# sch.net
KiCad netlist of a schematic drawn in EasyEDA
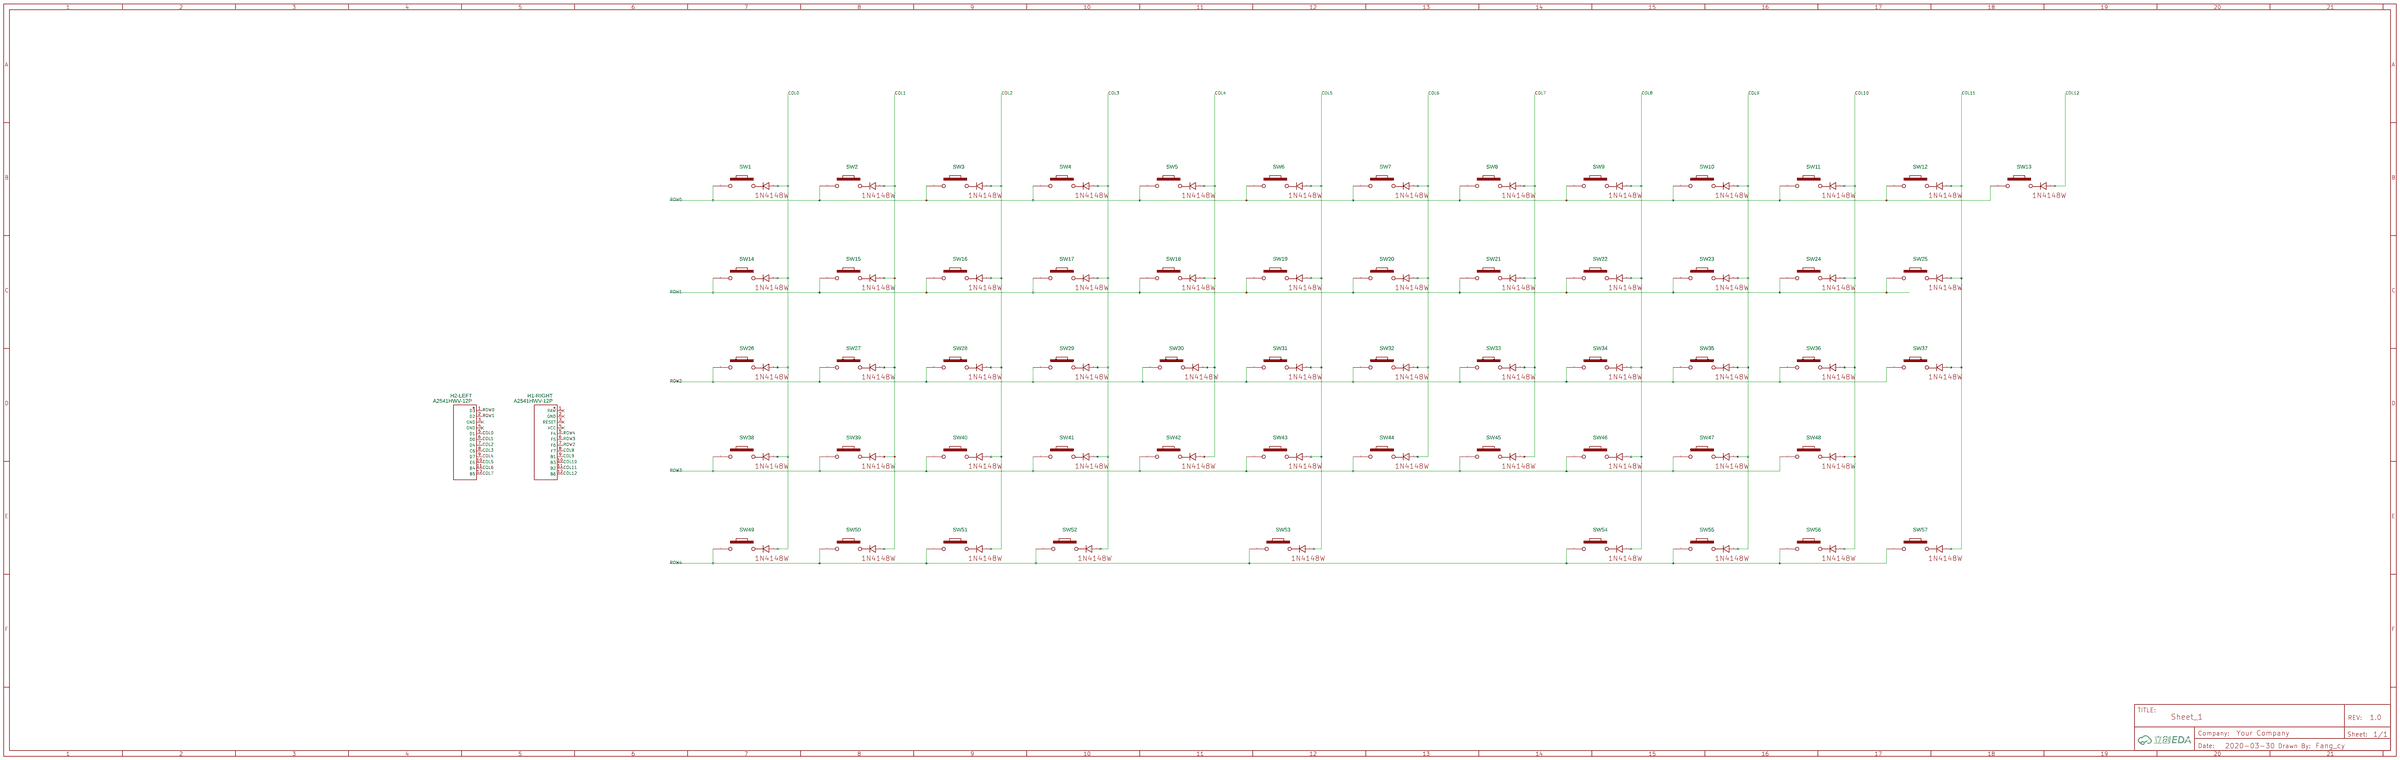
[diagram p0: schematic sheet]

(export (version "E")
  (design (tool "Eeschema 10.0.6"))
  (components
    (comp (ref "H1-RIGHT")
      (value "A2541HWV-12P")
      (fields (field (name "BOM_Supplier Part") "C225509"))
      (libsource (lib "") (part "A2541HWV-12P"))
    )
    (comp (ref "H2-LEFT")
      (value "A2541HWV-12P")
      (fields (field (name "BOM_Supplier Part") "C225509"))
      (libsource (lib "") (part "A2541HWV-12P_1"))
    )
    (comp (ref "SW1")
      (value "CHERRY-Kaih+diode")
      (fields (field (name "BOM_Manufacturer Part") "00"))
      (libsource (lib "") (part "CHERRY-Kaih+diode"))
    )
    (comp (ref "SW2")
      (value "CHERRY-Kaih+diode")
      (fields (field (name "BOM_Manufacturer Part") "00"))
      (libsource (lib "") (part "CHERRY-Kaih+diode"))
    )
    (comp (ref "SW3")
      (value "CHERRY-Kaih+diode")
      (fields (field (name "BOM_Manufacturer Part") "00"))
      (libsource (lib "") (part "CHERRY-Kaih+diode"))
    )
    (comp (ref "SW4")
      (value "CHERRY-Kaih+diode")
      (fields (field (name "BOM_Manufacturer Part") "00"))
      (libsource (lib "") (part "CHERRY-Kaih+diode"))
    )
    (comp (ref "SW5")
      (value "CHERRY-Kaih+diode")
      (fields (field (name "BOM_Manufacturer Part") "00"))
      (libsource (lib "") (part "CHERRY-Kaih+diode"))
    )
    (comp (ref "SW6")
      (value "CHERRY-Kaih+diode")
      (fields (field (name "BOM_Manufacturer Part") "00"))
      (libsource (lib "") (part "CHERRY-Kaih+diode"))
    )
    (comp (ref "SW7")
      (value "CHERRY-Kaih+diode")
      (fields (field (name "BOM_Manufacturer Part") "00"))
      (libsource (lib "") (part "CHERRY-Kaih+diode"))
    )
    (comp (ref "SW8")
      (value "CHERRY-Kaih+diode")
      (fields (field (name "BOM_Manufacturer Part") "00"))
      (libsource (lib "") (part "CHERRY-Kaih+diode"))
    )
    (comp (ref "SW9")
      (value "CHERRY-Kaih+diode")
      (fields (field (name "BOM_Manufacturer Part") "00"))
      (libsource (lib "") (part "CHERRY-Kaih+diode"))
    )
    (comp (ref "SW10")
      (value "CHERRY-Kaih+diode")
      (fields (field (name "BOM_Manufacturer Part") "00"))
      (libsource (lib "") (part "CHERRY-Kaih+diode"))
    )
    (comp (ref "SW11")
      (value "CHERRY-Kaih+diode")
      (fields (field (name "BOM_Manufacturer Part") "00"))
      (libsource (lib "") (part "CHERRY-Kaih+diode"))
    )
    (comp (ref "SW12")
      (value "CHERRY-Kaih+diode")
      (fields (field (name "BOM_Manufacturer Part") "00"))
      (libsource (lib "") (part "CHERRY-Kaih+diode"))
    )
    (comp (ref "SW13")
      (value "CHERRY-Kaih+diode")
      (fields (field (name "BOM_Manufacturer Part") "00"))
      (libsource (lib "") (part "CHERRY-Kaih+diode"))
    )
    (comp (ref "SW14")
      (value "CHERRY-Kaih+diode")
      (fields (field (name "BOM_Manufacturer Part") "00"))
      (libsource (lib "") (part "CHERRY-Kaih+diode"))
    )
    (comp (ref "SW15")
      (value "CHERRY-Kaih+diode")
      (fields (field (name "BOM_Manufacturer Part") "00"))
      (libsource (lib "") (part "CHERRY-Kaih+diode"))
    )
    (comp (ref "SW16")
      (value "CHERRY-Kaih+diode")
      (fields (field (name "BOM_Manufacturer Part") "00"))
      (libsource (lib "") (part "CHERRY-Kaih+diode"))
    )
    (comp (ref "SW17")
      (value "CHERRY-Kaih+diode")
      (fields (field (name "BOM_Manufacturer Part") "00"))
      (libsource (lib "") (part "CHERRY-Kaih+diode"))
    )
    (comp (ref "SW18")
      (value "CHERRY-Kaih+diode")
      (fields (field (name "BOM_Manufacturer Part") "00"))
      (libsource (lib "") (part "CHERRY-Kaih+diode"))
    )
    (comp (ref "SW19")
      (value "CHERRY-Kaih+diode")
      (fields (field (name "BOM_Manufacturer Part") "00"))
      (libsource (lib "") (part "CHERRY-Kaih+diode"))
    )
    (comp (ref "SW20")
      (value "CHERRY-Kaih+diode")
      (fields (field (name "BOM_Manufacturer Part") "00"))
      (libsource (lib "") (part "CHERRY-Kaih+diode"))
    )
    (comp (ref "SW21")
      (value "CHERRY-Kaih+diode")
      (fields (field (name "BOM_Manufacturer Part") "00"))
      (libsource (lib "") (part "CHERRY-Kaih+diode"))
    )
    (comp (ref "SW22")
      (value "CHERRY-Kaih+diode")
      (fields (field (name "BOM_Manufacturer Part") "00"))
      (libsource (lib "") (part "CHERRY-Kaih+diode"))
    )
    (comp (ref "SW23")
      (value "CHERRY-Kaih+diode")
      (fields (field (name "BOM_Manufacturer Part") "00"))
      (libsource (lib "") (part "CHERRY-Kaih+diode"))
    )
    (comp (ref "SW24")
      (value "CHERRY-Kaih+diode")
      (fields (field (name "BOM_Manufacturer Part") "00"))
      (libsource (lib "") (part "CHERRY-Kaih+diode"))
    )
    (comp (ref "SW25")
      (value "CHERRY-Kaih+diode")
      (fields (field (name "BOM_Manufacturer Part") "00"))
      (libsource (lib "") (part "CHERRY-Kaih+diode"))
    )
    (comp (ref "SW26")
      (value "CHERRY-Kaih+diode")
      (fields (field (name "BOM_Manufacturer Part") "00"))
      (libsource (lib "") (part "CHERRY-Kaih+diode_2"))
    )
    (comp (ref "SW27")
      (value "CHERRY-Kaih+diode")
      (fields (field (name "BOM_Manufacturer Part") "00"))
      (libsource (lib "") (part "CHERRY-Kaih+diode_2"))
    )
    (comp (ref "SW28")
      (value "CHERRY-Kaih+diode")
      (fields (field (name "BOM_Manufacturer Part") "00"))
      (libsource (lib "") (part "CHERRY-Kaih+diode_2"))
    )
    (comp (ref "SW29")
      (value "CHERRY-Kaih+diode")
      (fields (field (name "BOM_Manufacturer Part") "00"))
      (libsource (lib "") (part "CHERRY-Kaih+diode_2"))
    )
    (comp (ref "SW30")
      (value "CHERRY-Kaih+diode")
      (fields (field (name "BOM_Manufacturer Part") "00"))
      (libsource (lib "") (part "CHERRY-Kaih+diode_2"))
    )
    (comp (ref "SW31")
      (value "CHERRY-Kaih+diode")
      (fields (field (name "BOM_Manufacturer Part") "00"))
      (libsource (lib "") (part "CHERRY-Kaih+diode_2"))
    )
    (comp (ref "SW32")
      (value "CHERRY-Kaih+diode")
      (fields (field (name "BOM_Manufacturer Part") "00"))
      (libsource (lib "") (part "CHERRY-Kaih+diode_2"))
    )
    (comp (ref "SW33")
      (value "CHERRY-Kaih+diode")
      (fields (field (name "BOM_Manufacturer Part") "00"))
      (libsource (lib "") (part "CHERRY-Kaih+diode_2"))
    )
    (comp (ref "SW34")
      (value "CHERRY-Kaih+diode")
      (fields (field (name "BOM_Manufacturer Part") "00"))
      (libsource (lib "") (part "CHERRY-Kaih+diode_2"))
    )
    (comp (ref "SW35")
      (value "CHERRY-Kaih+diode")
      (fields (field (name "BOM_Manufacturer Part") "00"))
      (libsource (lib "") (part "CHERRY-Kaih+diode_2"))
    )
    (comp (ref "SW36")
      (value "CHERRY-Kaih+diode")
      (fields (field (name "BOM_Manufacturer Part") "00"))
      (libsource (lib "") (part "CHERRY-Kaih+diode_2"))
    )
    (comp (ref "SW37")
      (value "CHERRY-Kaih+diode")
      (fields (field (name "BOM_Manufacturer Part") "00"))
      (libsource (lib "") (part "CHERRY-Kaih+diode_2"))
    )
    (comp (ref "SW38")
      (value "CHERRY-Kaih+diode")
      (fields (field (name "BOM_Manufacturer Part") "00"))
      (libsource (lib "") (part "CHERRY-Kaih+diode"))
    )
    (comp (ref "SW39")
      (value "CHERRY-Kaih+diode")
      (fields (field (name "BOM_Manufacturer Part") "00"))
      (libsource (lib "") (part "CHERRY-Kaih+diode"))
    )
    (comp (ref "SW40")
      (value "CHERRY-Kaih+diode")
      (fields (field (name "BOM_Manufacturer Part") "00"))
      (libsource (lib "") (part "CHERRY-Kaih+diode"))
    )
    (comp (ref "SW41")
      (value "CHERRY-Kaih+diode")
      (fields (field (name "BOM_Manufacturer Part") "00"))
      (libsource (lib "") (part "CHERRY-Kaih+diode"))
    )
    (comp (ref "SW42")
      (value "CHERRY-Kaih+diode")
      (fields (field (name "BOM_Manufacturer Part") "00"))
      (libsource (lib "") (part "CHERRY-Kaih+diode"))
    )
    (comp (ref "SW43")
      (value "CHERRY-Kaih+diode")
      (fields (field (name "BOM_Manufacturer Part") "00"))
      (libsource (lib "") (part "CHERRY-Kaih+diode"))
    )
    (comp (ref "SW44")
      (value "CHERRY-Kaih+diode")
      (fields (field (name "BOM_Manufacturer Part") "00"))
      (libsource (lib "") (part "CHERRY-Kaih+diode"))
    )
    (comp (ref "SW45")
      (value "CHERRY-Kaih+diode")
      (fields (field (name "BOM_Manufacturer Part") "00"))
      (libsource (lib "") (part "CHERRY-Kaih+diode"))
    )
    (comp (ref "SW46")
      (value "CHERRY-Kaih+diode")
      (fields (field (name "BOM_Manufacturer Part") "00"))
      (libsource (lib "") (part "CHERRY-Kaih+diode"))
    )
    (comp (ref "SW47")
      (value "CHERRY-Kaih+diode")
      (fields (field (name "BOM_Manufacturer Part") "00"))
      (libsource (lib "") (part "CHERRY-Kaih+diode"))
    )
    (comp (ref "SW48")
      (value "CHERRY-Kaih+diode")
      (fields (field (name "BOM_Manufacturer Part") "00"))
      (libsource (lib "") (part "CHERRY-Kaih+diode"))
    )
    (comp (ref "SW49")
      (value "CHERRY-Kaih+diode")
      (fields (field (name "BOM_Manufacturer Part") "00"))
      (libsource (lib "") (part "CHERRY-Kaih+diode_1"))
    )
    (comp (ref "SW50")
      (value "CHERRY-Kaih+diode")
      (fields (field (name "BOM_Manufacturer Part") "00"))
      (libsource (lib "") (part "CHERRY-Kaih+diode_1"))
    )
    (comp (ref "SW51")
      (value "CHERRY-Kaih+diode")
      (fields (field (name "BOM_Manufacturer Part") "00"))
      (libsource (lib "") (part "CHERRY-Kaih+diode_1"))
    )
    (comp (ref "SW52")
      (value "CHERRY-Kaih+diode")
      (fields (field (name "BOM_Manufacturer Part") "00"))
      (libsource (lib "") (part "CHERRY-Kaih+diode_1"))
    )
    (comp (ref "SW53")
      (value "CHERRY-Kaih+diode")
      (fields (field (name "BOM_Manufacturer Part") "00"))
      (libsource (lib "") (part "CHERRY-Kaih+diode_1"))
    )
    (comp (ref "SW54")
      (value "CHERRY-Kaih+diode")
      (fields (field (name "BOM_Manufacturer Part") "00"))
      (libsource (lib "") (part "CHERRY-Kaih+diode_1"))
    )
    (comp (ref "SW55")
      (value "CHERRY-Kaih+diode")
      (fields (field (name "BOM_Manufacturer Part") "00"))
      (libsource (lib "") (part "CHERRY-Kaih+diode_1"))
    )
    (comp (ref "SW56")
      (value "CHERRY-Kaih+diode")
      (fields (field (name "BOM_Manufacturer Part") "00"))
      (libsource (lib "") (part "CHERRY-Kaih+diode_1"))
    )
    (comp (ref "SW57")
      (value "CHERRY-Kaih+diode")
      (fields (field (name "BOM_Manufacturer Part") "00"))
      (libsource (lib "") (part "CHERRY-Kaih+diode_1"))
    )
  )
  (nets
    (net (code "1") (name "/COL0") (class "Default")
      (node (ref "H2-LEFT") (pin "5") (pinfunction "D1_5") (pintype "unspecified"))
      (node (ref "SW1") (pin "col") (pinfunction "col_col") (pintype "unspecified"))
      (node (ref "SW14") (pin "col") (pinfunction "col_col") (pintype "unspecified"))
      (node (ref "SW26") (pin "col") (pinfunction "col_col") (pintype "unspecified"))
      (node (ref "SW38") (pin "col") (pinfunction "col_col") (pintype "unspecified"))
      (node (ref "SW49") (pin "col") (pinfunction "col_col") (pintype "unspecified"))
    )
    (net (code "2") (name "/COL1") (class "Default")
      (node (ref "H2-LEFT") (pin "6") (pinfunction "D0_6") (pintype "unspecified"))
      (node (ref "SW15") (pin "col") (pinfunction "col_col") (pintype "unspecified"))
      (node (ref "SW2") (pin "col") (pinfunction "col_col") (pintype "unspecified"))
      (node (ref "SW27") (pin "col") (pinfunction "col_col") (pintype "unspecified"))
      (node (ref "SW39") (pin "col") (pinfunction "col_col") (pintype "unspecified"))
      (node (ref "SW50") (pin "col") (pinfunction "col_col") (pintype "unspecified"))
    )
    (net (code "3") (name "/COL2") (class "Default")
      (node (ref "H2-LEFT") (pin "7") (pinfunction "D4_7") (pintype "unspecified"))
      (node (ref "SW16") (pin "col") (pinfunction "col_col") (pintype "unspecified"))
      (node (ref "SW28") (pin "col") (pinfunction "col_col") (pintype "unspecified"))
      (node (ref "SW3") (pin "col") (pinfunction "col_col") (pintype "unspecified"))
      (node (ref "SW40") (pin "col") (pinfunction "col_col") (pintype "unspecified"))
      (node (ref "SW51") (pin "col") (pinfunction "col_col") (pintype "unspecified"))
    )
    (net (code "4") (name "/COL3") (class "Default")
      (node (ref "H2-LEFT") (pin "8") (pinfunction "C6_8") (pintype "unspecified"))
      (node (ref "SW17") (pin "col") (pinfunction "col_col") (pintype "unspecified"))
      (node (ref "SW29") (pin "col") (pinfunction "col_col") (pintype "unspecified"))
      (node (ref "SW4") (pin "col") (pinfunction "col_col") (pintype "unspecified"))
      (node (ref "SW41") (pin "col") (pinfunction "col_col") (pintype "unspecified"))
      (node (ref "SW52") (pin "col") (pinfunction "col_col") (pintype "unspecified"))
    )
    (net (code "5") (name "/COL4") (class "Default")
      (node (ref "H2-LEFT") (pin "9") (pinfunction "D7_9") (pintype "unspecified"))
      (node (ref "SW18") (pin "col") (pinfunction "col_col") (pintype "unspecified"))
      (node (ref "SW30") (pin "col") (pinfunction "col_col") (pintype "unspecified"))
      (node (ref "SW42") (pin "col") (pinfunction "col_col") (pintype "unspecified"))
      (node (ref "SW5") (pin "col") (pinfunction "col_col") (pintype "unspecified"))
    )
    (net (code "6") (name "/COL5") (class "Default")
      (node (ref "H2-LEFT") (pin "10") (pinfunction "E6_10") (pintype "unspecified"))
      (node (ref "SW19") (pin "col") (pinfunction "col_col") (pintype "unspecified"))
      (node (ref "SW31") (pin "col") (pinfunction "col_col") (pintype "unspecified"))
      (node (ref "SW43") (pin "col") (pinfunction "col_col") (pintype "unspecified"))
      (node (ref "SW53") (pin "col") (pinfunction "col_col") (pintype "unspecified"))
      (node (ref "SW6") (pin "col") (pinfunction "col_col") (pintype "unspecified"))
    )
    (net (code "7") (name "/COL6") (class "Default")
      (node (ref "H2-LEFT") (pin "11") (pinfunction "B4_11") (pintype "unspecified"))
      (node (ref "SW20") (pin "col") (pinfunction "col_col") (pintype "unspecified"))
      (node (ref "SW32") (pin "col") (pinfunction "col_col") (pintype "unspecified"))
      (node (ref "SW44") (pin "col") (pinfunction "col_col") (pintype "unspecified"))
      (node (ref "SW7") (pin "col") (pinfunction "col_col") (pintype "unspecified"))
    )
    (net (code "8") (name "/COL7") (class "Default")
      (node (ref "H2-LEFT") (pin "12") (pinfunction "B5_12") (pintype "unspecified"))
      (node (ref "SW21") (pin "col") (pinfunction "col_col") (pintype "unspecified"))
      (node (ref "SW33") (pin "col") (pinfunction "col_col") (pintype "unspecified"))
      (node (ref "SW45") (pin "col") (pinfunction "col_col") (pintype "unspecified"))
      (node (ref "SW8") (pin "col") (pinfunction "col_col") (pintype "unspecified"))
    )
    (net (code "9") (name "/COL8") (class "Default")
      (node (ref "H1-RIGHT") (pin "8") (pinfunction "F7_8") (pintype "unspecified"))
      (node (ref "SW22") (pin "col") (pinfunction "col_col") (pintype "unspecified"))
      (node (ref "SW34") (pin "col") (pinfunction "col_col") (pintype "unspecified"))
      (node (ref "SW46") (pin "col") (pinfunction "col_col") (pintype "unspecified"))
      (node (ref "SW54") (pin "col") (pinfunction "col_col") (pintype "unspecified"))
      (node (ref "SW9") (pin "col") (pinfunction "col_col") (pintype "unspecified"))
    )
    (net (code "10") (name "/COL9") (class "Default")
      (node (ref "H1-RIGHT") (pin "9") (pinfunction "B1_9") (pintype "unspecified"))
      (node (ref "SW10") (pin "col") (pinfunction "col_col") (pintype "unspecified"))
      (node (ref "SW23") (pin "col") (pinfunction "col_col") (pintype "unspecified"))
      (node (ref "SW35") (pin "col") (pinfunction "col_col") (pintype "unspecified"))
      (node (ref "SW47") (pin "col") (pinfunction "col_col") (pintype "unspecified"))
      (node (ref "SW55") (pin "col") (pinfunction "col_col") (pintype "unspecified"))
    )
    (net (code "11") (name "/COL10") (class "Default")
      (node (ref "H1-RIGHT") (pin "10") (pinfunction "B3_10") (pintype "unspecified"))
      (node (ref "SW11") (pin "col") (pinfunction "col_col") (pintype "unspecified"))
      (node (ref "SW24") (pin "col") (pinfunction "col_col") (pintype "unspecified"))
      (node (ref "SW36") (pin "col") (pinfunction "col_col") (pintype "unspecified"))
      (node (ref "SW48") (pin "col") (pinfunction "col_col") (pintype "unspecified"))
      (node (ref "SW56") (pin "col") (pinfunction "col_col") (pintype "unspecified"))
    )
    (net (code "12") (name "/COL11") (class "Default")
      (node (ref "H1-RIGHT") (pin "11") (pinfunction "B2_11") (pintype "unspecified"))
      (node (ref "SW12") (pin "col") (pinfunction "col_col") (pintype "unspecified"))
      (node (ref "SW25") (pin "col") (pinfunction "col_col") (pintype "unspecified"))
      (node (ref "SW37") (pin "col") (pinfunction "col_col") (pintype "unspecified"))
      (node (ref "SW57") (pin "col") (pinfunction "col_col") (pintype "unspecified"))
    )
    (net (code "13") (name "/COL12") (class "Default")
      (node (ref "H1-RIGHT") (pin "12") (pinfunction "B6_12") (pintype "unspecified"))
      (node (ref "SW13") (pin "col") (pinfunction "col_col") (pintype "unspecified"))
    )
    (net (code "14") (name "/ROW0") (class "Default")
      (node (ref "H2-LEFT") (pin "1") (pinfunction "D3_1") (pintype "unspecified"))
      (node (ref "SW1") (pin "row") (pinfunction "row_row") (pintype "unspecified"))
      (node (ref "SW10") (pin "row") (pinfunction "row_row") (pintype "unspecified"))
      (node (ref "SW11") (pin "row") (pinfunction "row_row") (pintype "unspecified"))
      (node (ref "SW12") (pin "row") (pinfunction "row_row") (pintype "unspecified"))
      (node (ref "SW13") (pin "row") (pinfunction "row_row") (pintype "unspecified"))
      (node (ref "SW2") (pin "row") (pinfunction "row_row") (pintype "unspecified"))
      (node (ref "SW3") (pin "row") (pinfunction "row_row") (pintype "unspecified"))
      (node (ref "SW4") (pin "row") (pinfunction "row_row") (pintype "unspecified"))
      (node (ref "SW5") (pin "row") (pinfunction "row_row") (pintype "unspecified"))
      (node (ref "SW6") (pin "row") (pinfunction "row_row") (pintype "unspecified"))
      (node (ref "SW7") (pin "row") (pinfunction "row_row") (pintype "unspecified"))
      (node (ref "SW8") (pin "row") (pinfunction "row_row") (pintype "unspecified"))
      (node (ref "SW9") (pin "row") (pinfunction "row_row") (pintype "unspecified"))
    )
    (net (code "15") (name "/ROW1") (class "Default")
      (node (ref "H2-LEFT") (pin "2") (pinfunction "D2_2") (pintype "unspecified"))
      (node (ref "SW14") (pin "row") (pinfunction "row_row") (pintype "unspecified"))
      (node (ref "SW15") (pin "row") (pinfunction "row_row") (pintype "unspecified"))
      (node (ref "SW16") (pin "row") (pinfunction "row_row") (pintype "unspecified"))
      (node (ref "SW17") (pin "row") (pinfunction "row_row") (pintype "unspecified"))
      (node (ref "SW18") (pin "row") (pinfunction "row_row") (pintype "unspecified"))
      (node (ref "SW19") (pin "row") (pinfunction "row_row") (pintype "unspecified"))
      (node (ref "SW20") (pin "row") (pinfunction "row_row") (pintype "unspecified"))
      (node (ref "SW21") (pin "row") (pinfunction "row_row") (pintype "unspecified"))
      (node (ref "SW22") (pin "row") (pinfunction "row_row") (pintype "unspecified"))
      (node (ref "SW23") (pin "row") (pinfunction "row_row") (pintype "unspecified"))
      (node (ref "SW24") (pin "row") (pinfunction "row_row") (pintype "unspecified"))
      (node (ref "SW25") (pin "row") (pinfunction "row_row") (pintype "unspecified"))
    )
    (net (code "16") (name "/ROW2") (class "Default")
      (node (ref "H1-RIGHT") (pin "7") (pinfunction "F6_7") (pintype "unspecified"))
      (node (ref "SW26") (pin "row") (pinfunction "row_row") (pintype "unspecified"))
      (node (ref "SW27") (pin "row") (pinfunction "row_row") (pintype "unspecified"))
      (node (ref "SW28") (pin "row") (pinfunction "row_row") (pintype "unspecified"))
      (node (ref "SW29") (pin "row") (pinfunction "row_row") (pintype "unspecified"))
      (node (ref "SW30") (pin "row") (pinfunction "row_row") (pintype "unspecified"))
      (node (ref "SW31") (pin "row") (pinfunction "row_row") (pintype "unspecified"))
      (node (ref "SW32") (pin "row") (pinfunction "row_row") (pintype "unspecified"))
      (node (ref "SW33") (pin "row") (pinfunction "row_row") (pintype "unspecified"))
      (node (ref "SW34") (pin "row") (pinfunction "row_row") (pintype "unspecified"))
      (node (ref "SW35") (pin "row") (pinfunction "row_row") (pintype "unspecified"))
      (node (ref "SW36") (pin "row") (pinfunction "row_row") (pintype "unspecified"))
      (node (ref "SW37") (pin "row") (pinfunction "row_row") (pintype "unspecified"))
    )
    (net (code "17") (name "/ROW3") (class "Default")
      (node (ref "H1-RIGHT") (pin "6") (pinfunction "F5_6") (pintype "unspecified"))
      (node (ref "SW38") (pin "row") (pinfunction "row_row") (pintype "unspecified"))
      (node (ref "SW39") (pin "row") (pinfunction "row_row") (pintype "unspecified"))
      (node (ref "SW40") (pin "row") (pinfunction "row_row") (pintype "unspecified"))
      (node (ref "SW41") (pin "row") (pinfunction "row_row") (pintype "unspecified"))
      (node (ref "SW42") (pin "row") (pinfunction "row_row") (pintype "unspecified"))
      (node (ref "SW43") (pin "row") (pinfunction "row_row") (pintype "unspecified"))
      (node (ref "SW44") (pin "row") (pinfunction "row_row") (pintype "unspecified"))
      (node (ref "SW45") (pin "row") (pinfunction "row_row") (pintype "unspecified"))
      (node (ref "SW46") (pin "row") (pinfunction "row_row") (pintype "unspecified"))
      (node (ref "SW47") (pin "row") (pinfunction "row_row") (pintype "unspecified"))
      (node (ref "SW48") (pin "row") (pinfunction "row_row") (pintype "unspecified"))
    )
    (net (code "18") (name "/ROW4") (class "Default")
      (node (ref "H1-RIGHT") (pin "5") (pinfunction "F4_5") (pintype "unspecified"))
      (node (ref "SW49") (pin "row") (pinfunction "row_row") (pintype "unspecified"))
      (node (ref "SW50") (pin "row") (pinfunction "row_row") (pintype "unspecified"))
      (node (ref "SW51") (pin "row") (pinfunction "row_row") (pintype "unspecified"))
      (node (ref "SW52") (pin "row") (pinfunction "row_row") (pintype "unspecified"))
      (node (ref "SW53") (pin "row") (pinfunction "row_row") (pintype "unspecified"))
      (node (ref "SW54") (pin "row") (pinfunction "row_row") (pintype "unspecified"))
      (node (ref "SW55") (pin "row") (pinfunction "row_row") (pintype "unspecified"))
      (node (ref "SW56") (pin "row") (pinfunction "row_row") (pintype "unspecified"))
      (node (ref "SW57") (pin "row") (pinfunction "row_row") (pintype "unspecified"))
    )
    (net (code "19") (name "unconnected-(H1-RIGHT-GND-Pad2)") (class "Default")
      (node (ref "H1-RIGHT") (pin "2") (pinfunction "GND_2") (pintype "unspecified+no_connect"))
    )
    (net (code "20") (name "unconnected-(H1-RIGHT-RAW-Pad1)") (class "Default")
      (node (ref "H1-RIGHT") (pin "1") (pinfunction "RAW_1") (pintype "unspecified+no_connect"))
    )
    (net (code "21") (name "unconnected-(H1-RIGHT-RESET-Pad3)") (class "Default")
      (node (ref "H1-RIGHT") (pin "3") (pinfunction "RESET_3") (pintype "unspecified+no_connect"))
    )
    (net (code "22") (name "unconnected-(H1-RIGHT-VCC-Pad4)") (class "Default")
      (node (ref "H1-RIGHT") (pin "4") (pinfunction "VCC_4") (pintype "unspecified+no_connect"))
    )
    (net (code "23") (name "unconnected-(H2-LEFT-GND-Pad3)") (class "Default")
      (node (ref "H2-LEFT") (pin "3") (pinfunction "GND_3") (pintype "unspecified+no_connect"))
    )
    (net (code "24") (name "unconnected-(H2-LEFT-GND-Pad4)") (class "Default")
      (node (ref "H2-LEFT") (pin "4") (pinfunction "GND_4") (pintype "unspecified+no_connect"))
    )
  )
)
